# Mach_dieu_khien_dong_co_dc_luu_tru.net
KiCad netlist of a schematic drawn in Altium Designer
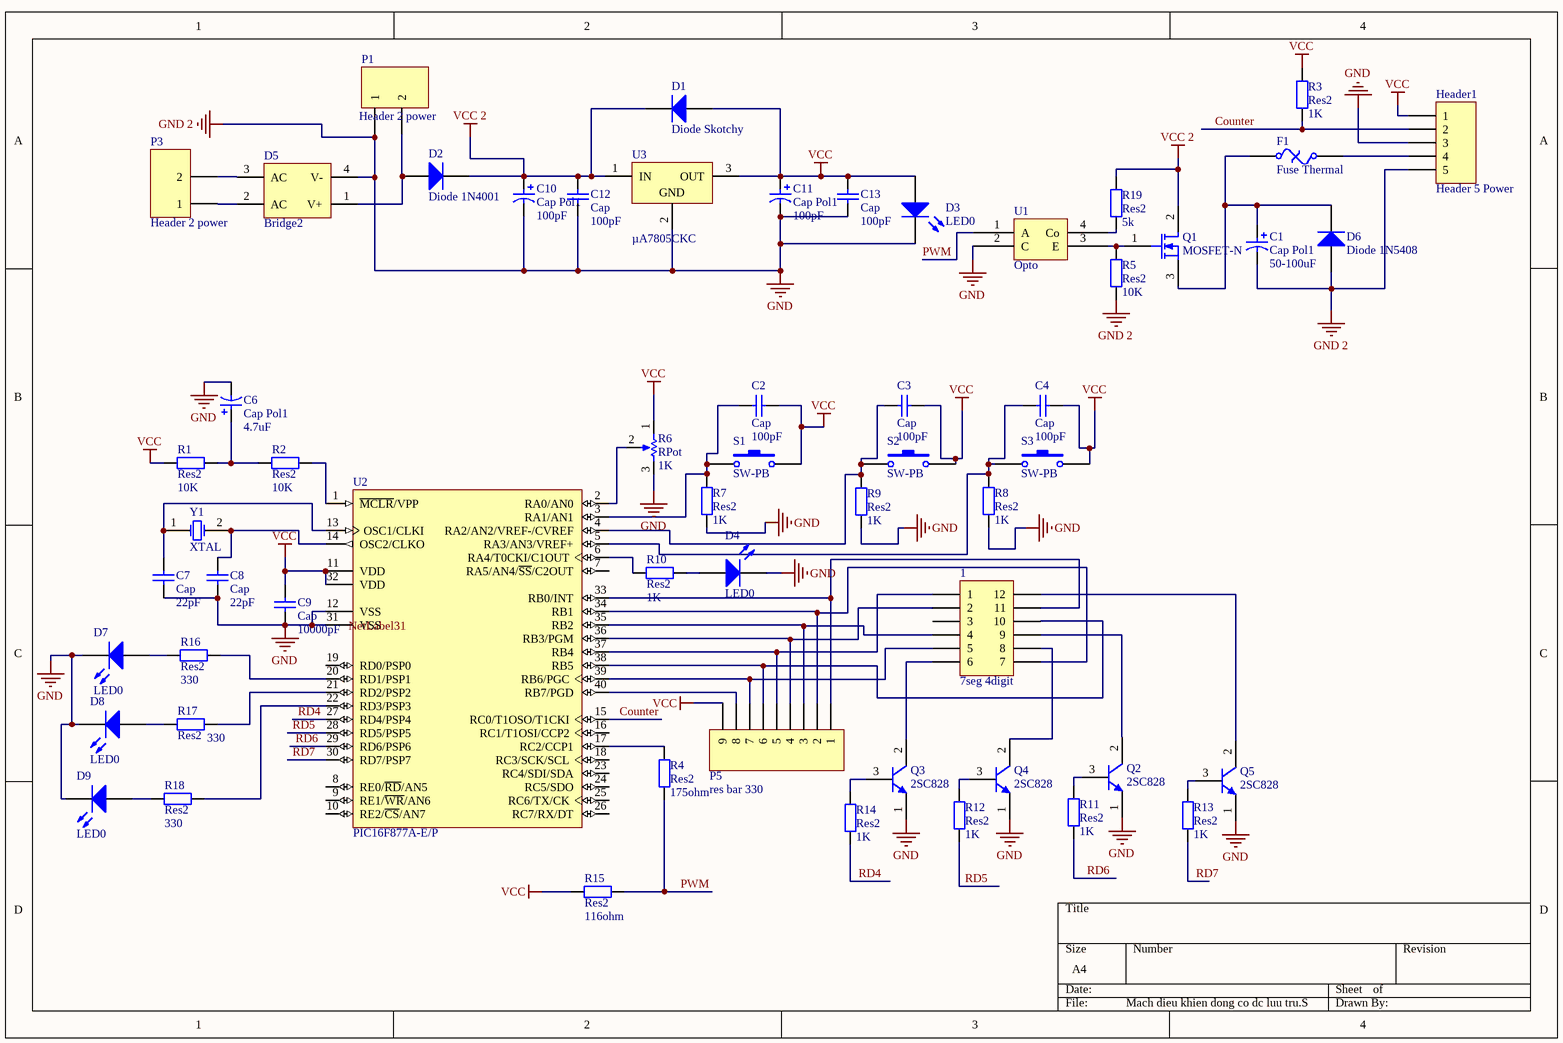
[diagram p0: Mach dieu khien dong co dc luu tru.SchDoc]

(export (version "E")
  (design (tool "Eeschema 10.0.6"))
  (components
    (comp (ref "1")
      (value "7seg 4digit")
      (footprint "LEDDIP-12/QUAD")
      (description "Header, 6-Pin, Dual row")
      (fields (field (name "PUBLISHER") "Altium Limited"))
      (libsource (lib "Manh") (part "7seg 4digit"))
    )
    (comp (ref "C1")
      (value "Cap Pol1")
      (footprint "CAPPR5-5x7")
      (description "Polarized Capacitor (Radial)")
      (fields (field (name "ALTIUM_VALUE") "50-100uF") (field (name "PUBLISHER") "Altium Limited"))
      (libsource (lib "Manh") (part "Cap Pol1"))
    )
    (comp (ref "C2")
      (value "Cap")
      (footprint "CAPNTO3.18-4.83x2.67")
      (description "Capacitor")
      (fields (field (name "ALTIUM_VALUE") "100pF") (field (name "PUBLISHER") "Altium Limited"))
      (libsource (lib "Manh") (part "Cap"))
    )
    (comp (ref "C3")
      (value "Cap")
      (footprint "CAPNTO3.18-4.83x2.67")
      (description "Capacitor")
      (fields (field (name "ALTIUM_VALUE") "100pF") (field (name "PUBLISHER") "Altium Limited"))
      (libsource (lib "Manh") (part "Cap"))
    )
    (comp (ref "C4")
      (value "Cap")
      (footprint "CAPNTO3.18-4.83x2.67")
      (description "Capacitor")
      (fields (field (name "ALTIUM_VALUE") "100pF") (field (name "PUBLISHER") "Altium Limited"))
      (libsource (lib "Manh") (part "Cap"))
    )
    (comp (ref "C6")
      (value "Cap Pol1")
      (footprint "CAPPR2-5x15")
      (description "Polarized Capacitor (Radial)")
      (fields (field (name "ALTIUM_VALUE") "4.7uF") (field (name "PUBLISHER") "Altium Limited"))
      (libsource (lib "Manh") (part "Cap Pol1"))
    )
    (comp (ref "C7")
      (value "Cap")
      (footprint "CAPNTO3.18-4.83x2.67")
      (description "Capacitor")
      (fields (field (name "ALTIUM_VALUE") "22pF") (field (name "PUBLISHER") "Altium Limited"))
      (libsource (lib "Manh") (part "Cap"))
    )
    (comp (ref "C8")
      (value "Cap")
      (footprint "CAPNTO3.18-4.83x2.67")
      (description "Capacitor")
      (fields (field (name "ALTIUM_VALUE") "22pF") (field (name "PUBLISHER") "Altium Limited"))
      (libsource (lib "Manh") (part "Cap"))
    )
    (comp (ref "C9")
      (value "Cap")
      (footprint "CAPNTO3.18-4.83x2.67")
      (description "Capacitor")
      (fields (field (name "ALTIUM_VALUE") "10000pF") (field (name "PUBLISHER") "Altium Limited"))
      (libsource (lib "Manh") (part "Cap"))
    )
    (comp (ref "C10")
      (value "Cap Pol1")
      (footprint "CAPPR7.5-18x40")
      (description "Polarized Capacitor (Radial)")
      (fields (field (name "ALTIUM_VALUE") "100pF") (field (name "PUBLISHER") "Altium Limited"))
      (libsource (lib "Manh") (part "Cap Pol1"))
    )
    (comp (ref "C11")
      (value "Cap Pol1")
      (footprint "CAPPR3.5-8x5")
      (description "Polarized Capacitor (Radial)")
      (fields (field (name "ALTIUM_VALUE") "100pF") (field (name "PUBLISHER") "Altium Limited"))
      (libsource (lib "Manh") (part "Cap Pol1"))
    )
    (comp (ref "C12")
      (value "Cap")
      (footprint "CAPNTO3.18-4.83x2.67")
      (description "Capacitor")
      (fields (field (name "ALTIUM_VALUE") "100pF") (field (name "PUBLISHER") "Altium Limited"))
      (libsource (lib "Manh") (part "Cap"))
    )
    (comp (ref "C13")
      (value "Cap")
      (footprint "CAPNTO3.18-4.83x2.67")
      (description "Capacitor")
      (fields (field (name "ALTIUM_VALUE") "100pF") (field (name "PUBLISHER") "Altium Limited"))
      (libsource (lib "Manh") (part "Cap"))
    )
    (comp (ref "D1")
      (value "Diode Skotchy")
      (footprint "DO-41")
      (description "1 Amp General Purpose Rectifier")
      (fields (field (name "PUBLISHER") "Altium Limited"))
      (libsource (lib "Miscellaneous Devices") (part "Diode 1N4001"))
    )
    (comp (ref "D2")
      (value "Diode 1N4001")
      (footprint "DO-41")
      (description "1 Amp General Purpose Rectifier")
      (fields (field (name "PUBLISHER") "Altium Limited"))
      (libsource (lib "Miscellaneous Devices") (part "Diode 1N4001"))
    )
    (comp (ref "D3")
      (value "LED0")
      (footprint "CAPPR2-5x15")
      (description "Typical INFRARED GaAs LED")
      (fields (field (name "PUBLISHER") "Altium Limited"))
      (libsource (lib "Manh") (part "LED0"))
    )
    (comp (ref "D4")
      (value "LED0")
      (footprint "CAPPR2-5x15")
      (description "Typical INFRARED GaAs LED")
      (fields (field (name "PUBLISHER") "Altium Limited"))
      (libsource (lib "Manh") (part "LED0"))
    )
    (comp (ref "D5")
      (value "Bridge2")
      (footprint "SIP-P4/A6.8")
      (description "Diode Bridge")
      (fields (field (name "PUBLISHER") "Altium Limited"))
      (libsource (lib "Manh") (part "Bridge2"))
    )
    (comp (ref "D6")
      (value "Diode 1N5408")
      (footprint "DO-201AD")
      (description "3 Amp Medium Power Silicon Rectifier Diode")
      (fields (field (name "PUBLISHER") "Altium Limited"))
      (libsource (lib "Miscellaneous Devices") (part "Diode 1N5408"))
    )
    (comp (ref "D7")
      (value "LED0")
      (footprint "CAPPR2-5x15")
      (description "Typical INFRARED GaAs LED")
      (fields (field (name "PUBLISHER") "Altium Limited"))
      (libsource (lib "Manh") (part "LED0"))
    )
    (comp (ref "D8")
      (value "LED0")
      (footprint "CAPPR2-5x15")
      (description "Typical INFRARED GaAs LED")
      (fields (field (name "PUBLISHER") "Altium Limited"))
      (libsource (lib "Manh") (part "LED0"))
    )
    (comp (ref "D9")
      (value "LED0")
      (footprint "CAPPR2-5x15")
      (description "Typical INFRARED GaAs LED")
      (fields (field (name "PUBLISHER") "Altium Limited"))
      (libsource (lib "Manh") (part "LED0"))
    )
    (comp (ref "F1")
      (value "Fuse Thermal")
      (footprint "PIN-W2/E2.8")
      (description "Thermal Fuse")
      (fields (field (name "PUBLISHER") "Altium Limited"))
      (libsource (lib "Manh") (part "Fuse Thermal"))
    )
    (comp (ref "Header1")
      (value "Header 5 Power")
      (footprint "Header 5 Power")
      (fields (field (name "PUBLISHER") "Altium Limited"))
      (libsource (lib "Manh") (part "Header 5 Power"))
    )
    (comp (ref "P1")
      (value "Header 2 power")
      (footprint "conector 2x1 power")
      (description "Header, 4-Pin, Right Angle")
      (fields (field (name "PUBLISHER") "Altium Limited"))
      (libsource (lib "Manh") (part "Header 2 power"))
    )
    (comp (ref "P3")
      (value "Header 2 power")
      (footprint "conector 2x1 power")
      (description "Header, 2-Pin, Right Angle")
      (fields (field (name "PUBLISHER") "Altium Limited"))
      (libsource (lib "") (part "Header 2 power_1"))
    )
    (comp (ref "P5")
      (value "res bar 330")
      (footprint "HDR1X9")
      (description "Header, 9-Pin")
      (fields (field (name "PUBLISHER") "Altium Limited"))
      (libsource (lib "Miscellaneous Connectors") (part "Header 9"))
    )
    (comp (ref "Q1")
      (value "MOSFET-N")
      (footprint "E3-manh")
      (description "N-Channel MOSFET")
      (fields (field (name "PUBLISHER") "Altium Limited"))
      (libsource (lib "Manh") (part "MOSFET-N"))
    )
    (comp (ref "Q2")
      (value "2SC828")
      (footprint "TO-92-manh")
      (description "NPN General Purpose Amplifier")
      (fields (field (name "PUBLISHER") "Altium Limited"))
      (libsource (lib "Manh") (part "2SC828"))
    )
    (comp (ref "Q3")
      (value "2SC828")
      (footprint "TO-92-manh")
      (description "NPN General Purpose Amplifier")
      (fields (field (name "PUBLISHER") "Altium Limited"))
      (libsource (lib "Manh") (part "2SC828"))
    )
    (comp (ref "Q4")
      (value "2SC828")
      (footprint "TO-92-manh")
      (description "NPN General Purpose Amplifier")
      (fields (field (name "PUBLISHER") "Altium Limited"))
      (libsource (lib "Manh") (part "2SC828"))
    )
    (comp (ref "Q5")
      (value "2SC828")
      (footprint "TO-92-manh")
      (description "NPN General Purpose Amplifier")
      (fields (field (name "PUBLISHER") "Altium Limited"))
      (libsource (lib "Manh") (part "2SC828"))
    )
    (comp (ref "R1")
      (value "Res2")
      (footprint "AXIAL-0.4")
      (description "Resistor")
      (fields (field (name "ALTIUM_VALUE") "10K") (field (name "PUBLISHER") "Altium Limited"))
      (libsource (lib "") (part "Res2_2"))
    )
    (comp (ref "R2")
      (value "Res2")
      (footprint "AXIAL-0.4")
      (description "Resistor")
      (fields (field (name "ALTIUM_VALUE") "10K") (field (name "PUBLISHER") "Altium Limited"))
      (libsource (lib "") (part "Res2_2"))
    )
    (comp (ref "R3")
      (value "Res2")
      (footprint "AXIAL-0.4")
      (description "Resistor")
      (fields (field (name "ALTIUM_VALUE") "1K") (field (name "PUBLISHER") "Altium Limited"))
      (libsource (lib "") (part "Res2_3"))
    )
    (comp (ref "R4")
      (value "Res2")
      (footprint "AXIAL-0.4")
      (description "Resistor")
      (fields (field (name "ALTIUM_VALUE") "175ohm") (field (name "PUBLISHER") "Altium Limited"))
      (libsource (lib "") (part "Res2_1"))
    )
    (comp (ref "R5")
      (value "Res2")
      (footprint "AXIAL-0.4")
      (description "Resistor")
      (fields (field (name "ALTIUM_VALUE") "10K") (field (name "PUBLISHER") "Altium Limited"))
      (libsource (lib "") (part "Res2_1"))
    )
    (comp (ref "R6")
      (value "RPot")
      (footprint "Header 3 Power")
      (description "Potentiometer")
      (fields (field (name "ALTIUM_VALUE") "1K") (field (name "PUBLISHER") "Altium Limited"))
      (libsource (lib "Manh") (part "RPot"))
    )
    (comp (ref "R7")
      (value "Res2")
      (footprint "AXIAL-0.4")
      (description "Resistor")
      (fields (field (name "ALTIUM_VALUE") "1K") (field (name "PUBLISHER") "Altium Limited"))
      (libsource (lib "") (part "Res2_1"))
    )
    (comp (ref "R8")
      (value "Res2")
      (footprint "AXIAL-0.4")
      (description "Resistor")
      (fields (field (name "ALTIUM_VALUE") "1K") (field (name "PUBLISHER") "Altium Limited"))
      (libsource (lib "") (part "Res2_1"))
    )
    (comp (ref "R9")
      (value "Res2")
      (footprint "AXIAL-0.4")
      (description "Resistor")
      (fields (field (name "ALTIUM_VALUE") "1K") (field (name "PUBLISHER") "Altium Limited"))
      (libsource (lib "") (part "Res2_1"))
    )
    (comp (ref "R10")
      (value "Res2")
      (footprint "AXIAL-0.4")
      (description "Resistor")
      (fields (field (name "ALTIUM_VALUE") "1K") (field (name "PUBLISHER") "Altium Limited"))
      (libsource (lib "") (part "Res2_2"))
    )
    (comp (ref "R11")
      (value "Res2")
      (footprint "AXIAL-0.4")
      (description "Resistor")
      (fields (field (name "ALTIUM_VALUE") "1K") (field (name "PUBLISHER") "Altium Limited"))
      (libsource (lib "") (part "Res2_1"))
    )
    (comp (ref "R12")
      (value "Res2")
      (footprint "AXIAL-0.4")
      (description "Resistor")
      (fields (field (name "ALTIUM_VALUE") "1K") (field (name "PUBLISHER") "Altium Limited"))
      (libsource (lib "") (part "Res2_1"))
    )
    (comp (ref "R13")
      (value "Res2")
      (footprint "AXIAL-0.4")
      (description "Resistor")
      (fields (field (name "ALTIUM_VALUE") "1K") (field (name "PUBLISHER") "Altium Limited"))
      (libsource (lib "") (part "Res2_1"))
    )
    (comp (ref "R14")
      (value "Res2")
      (footprint "AXIAL-0.4")
      (description "Resistor")
      (fields (field (name "ALTIUM_VALUE") "1K") (field (name "PUBLISHER") "Altium Limited"))
      (libsource (lib "") (part "Res2_1"))
    )
    (comp (ref "R15")
      (value "Res2")
      (footprint "AXIAL-0.4")
      (description "Resistor")
      (fields (field (name "ALTIUM_VALUE") "116ohm") (field (name "PUBLISHER") "Altium Limited"))
      (libsource (lib "Manh") (part "Res2"))
    )
    (comp (ref "R16")
      (value "Res2")
      (footprint "AXIAL-0.4")
      (description "Resistor")
      (fields (field (name "ALTIUM_VALUE") "330") (field (name "PUBLISHER") "Altium Limited"))
      (libsource (lib "") (part "Res2_2"))
    )
    (comp (ref "R17")
      (value "Res2")
      (footprint "AXIAL-0.4")
      (description "Resistor")
      (fields (field (name "ALTIUM_VALUE") "330") (field (name "PUBLISHER") "Altium Limited"))
      (libsource (lib "") (part "Res2_2"))
    )
    (comp (ref "R18")
      (value "Res2")
      (footprint "AXIAL-0.4")
      (description "Resistor")
      (fields (field (name "ALTIUM_VALUE") "330") (field (name "PUBLISHER") "Altium Limited"))
      (libsource (lib "") (part "Res2_2"))
    )
    (comp (ref "R19")
      (value "Res2")
      (footprint "AXIAL-0.4")
      (description "Resistor")
      (fields (field (name "ALTIUM_VALUE") "5k") (field (name "PUBLISHER") "Altium Limited"))
      (libsource (lib "") (part "Res2_1"))
    )
    (comp (ref "S1")
      (value "SW-PB")
      (footprint "Button DIP4")
      (description "Switch")
      (fields (field (name "PUBLISHER") "Altium Limited"))
      (libsource (lib "Manh") (part "SW-PB"))
    )
    (comp (ref "S2")
      (value "SW-PB")
      (footprint "Button DIP4")
      (description "Switch")
      (fields (field (name "PUBLISHER") "Altium Limited"))
      (libsource (lib "Manh") (part "SW-PB"))
    )
    (comp (ref "S3")
      (value "SW-PB")
      (footprint "Button DIP4")
      (description "Switch")
      (fields (field (name "PUBLISHER") "Altium Limited"))
      (libsource (lib "Manh") (part "SW-PB"))
    )
    (comp (ref "U1") (value "Opto") (footprint "DIP-4") (libsource (lib "Manh") (part "Opto 1")))
    (comp (ref "U2")
      (value "PIC16F877A-E/P")
      (footprint "Microchip Footprints:PDIP600-40")
      (fields (field (name "PUBLISHER") "Altium Limited"))
      (libsource (lib "Manh") (part "PIC16F877A-E/P"))
    )
    (comp (ref "U3")
      (value "µA7805CKC")
      (footprint "SFM-T3/A4.7V")
      (description "Positive-Voltage Regulator")
      (fields (field (name "MANUFACTURER") "Texas Instruments") (field (name "PUBLISHER") "Altium Limited"))
      (libsource (lib "TI Power Mgt Voltage Regulator") (part "µA7805CKC"))
    )
    (comp (ref "Y1")
      (value "XTAL")
      (footprint "CAPR5-4X5")
      (description "Crystal Oscillator")
      (fields (field (name "PUBLISHER") "Altium Limited"))
      (libsource (lib "Manh") (part "XTAL"))
    )
  )
  (nets
    (net (code "1") (name "/Counter") (class "Default")
      (node (ref "Header1") (pin "2") (pinfunction "2_2") (pintype "passive"))
      (node (ref "R3") (pin "2") (pinfunction "2_2") (pintype "passive"))
      (node (ref "U2") (pin "15") (pinfunction "RC0/T1OSO/T1CKI_15") (pintype "bidirectional"))
    )
    (net (code "3") (name "/PWM") (class "Default")
      (node (ref "R15") (pin "1") (pinfunction "1_1") (pintype "passive"))
      (node (ref "R4") (pin "1") (pinfunction "1_1") (pintype "passive"))
      (node (ref "U1") (pin "1") (pinfunction "A_1") (pintype "passive"))
    )
    (net (code "4") (name "/RD4") (class "Default")
      (node (ref "R14") (pin "1") (pinfunction "1_1") (pintype "passive"))
      (node (ref "U2") (pin "27") (pinfunction "RD4/PSP4_27") (pintype "bidirectional"))
    )
    (net (code "5") (name "/RD5") (class "Default")
      (node (ref "R12") (pin "1") (pinfunction "1_1") (pintype "passive"))
      (node (ref "U2") (pin "28") (pinfunction "RD5/PSP5_28") (pintype "bidirectional"))
    )
    (net (code "6") (name "/RD6") (class "Default")
      (node (ref "R11") (pin "1") (pinfunction "1_1") (pintype "passive"))
      (node (ref "U2") (pin "29") (pinfunction "RD6/PSP6_29") (pintype "bidirectional"))
    )
    (net (code "7") (name "/RD7") (class "Default")
      (node (ref "R13") (pin "1") (pinfunction "1_1") (pintype "passive"))
      (node (ref "U2") (pin "30") (pinfunction "RD7/PSP7_30") (pintype "bidirectional"))
    )
    (net (code "8") (name "GND") (class "Default")
      (node (ref "C1") (pin "2") (pinfunction "2_2") (pintype "passive"))
      (node (ref "C10") (pin "2") (pinfunction "2_2") (pintype "passive"))
      (node (ref "C11") (pin "2") (pinfunction "2_2") (pintype "passive"))
      (node (ref "C12") (pin "1") (pinfunction "1_1") (pintype "passive"))
      (node (ref "C13") (pin "1") (pinfunction "1_1") (pintype "passive"))
      (node (ref "C6") (pin "2") (pinfunction "2_2") (pintype "passive"))
      (node (ref "C7") (pin "1") (pinfunction "1_1") (pintype "passive"))
      (node (ref "C8") (pin "1") (pinfunction "1_1") (pintype "passive"))
      (node (ref "C9") (pin "1") (pinfunction "1_1") (pintype "passive"))
      (node (ref "D3") (pin "2") (pinfunction "K_2") (pintype "passive"))
      (node (ref "D4") (pin "2") (pinfunction "K_2") (pintype "passive"))
      (node (ref "D5") (pin "4") (pinfunction "V-_4") (pintype "passive"))
      (node (ref "D6") (pin "1") (pinfunction "A_1") (pintype "passive"))
      (node (ref "D7") (pin "2") (pinfunction "K_2") (pintype "passive"))
      (node (ref "D8") (pin "2") (pinfunction "K_2") (pintype "passive"))
      (node (ref "D9") (pin "2") (pinfunction "K_2") (pintype "passive"))
      (node (ref "Header1") (pin "3") (pinfunction "3_3") (pintype "passive"))
      (node (ref "Header1") (pin "5") (pinfunction "5_5") (pintype "passive"))
      (node (ref "P1") (pin "1") (pinfunction "1_1") (pintype "passive"))
      (node (ref "Q2") (pin "1") (pinfunction "E_1") (pintype "passive"))
      (node (ref "Q3") (pin "1") (pinfunction "E_1") (pintype "passive"))
      (node (ref "Q4") (pin "1") (pinfunction "E_1") (pintype "passive"))
      (node (ref "Q5") (pin "1") (pinfunction "E_1") (pintype "passive"))
      (node (ref "R5") (pin "1") (pinfunction "1_1") (pintype "passive"))
      (node (ref "R6") (pin "3") (pinfunction "BOT_3") (pintype "passive"))
      (node (ref "R7") (pin "1") (pinfunction "1_1") (pintype "passive"))
      (node (ref "R8") (pin "1") (pinfunction "1_1") (pintype "passive"))
      (node (ref "R9") (pin "1") (pinfunction "1_1") (pintype "passive"))
      (node (ref "U1") (pin "2") (pinfunction "C_2") (pintype "passive"))
      (node (ref "U2") (pin "12") (pinfunction "VSS_12") (pintype "power_in"))
      (node (ref "U2") (pin "31") (pinfunction "VSS_31") (pintype "power_in"))
      (node (ref "U3") (pin "2") (pinfunction "GND_2") (pintype "power_in"))
    )
    (net (code "9") (name "Net-(C6-Pad1)") (class "Default")
      (node (ref "C6") (pin "1") (pinfunction "1_1") (pintype "passive"))
      (node (ref "R1") (pin "2") (pinfunction "2_2") (pintype "passive"))
      (node (ref "R2") (pin "1") (pinfunction "1_1") (pintype "passive"))
    )
    (net (code "10") (name "Net-(D2-A)") (class "Default")
      (node (ref "D2") (pin "1") (pinfunction "A_1") (pintype "passive"))
      (node (ref "D5") (pin "1") (pinfunction "V+_1") (pintype "passive"))
      (node (ref "P1") (pin "2") (pinfunction "2_2") (pintype "passive"))
    )
    (net (code "11") (name "Net-(D4-A)") (class "Default")
      (node (ref "D4") (pin "1") (pinfunction "A_1") (pintype "passive"))
      (node (ref "R10") (pin "2") (pinfunction "2_2") (pintype "passive"))
    )
    (net (code "12") (name "Net-(D5-AC-Pad2)") (class "Default")
      (node (ref "D5") (pin "2") (pinfunction "AC_2") (pintype "passive"))
      (node (ref "P3") (pin "1") (pinfunction "1_1") (pintype "passive"))
    )
    (net (code "13") (name "Net-(D5-AC-Pad3)") (class "Default")
      (node (ref "D5") (pin "3") (pinfunction "AC_3") (pintype "passive"))
      (node (ref "P3") (pin "2") (pinfunction "2_2") (pintype "passive"))
    )
    (net (code "14") (name "Net-(D6-K)") (class "Default")
      (node (ref "C1") (pin "1") (pinfunction "1_1") (pintype "passive"))
      (node (ref "D6") (pin "2") (pinfunction "K_2") (pintype "passive"))
      (node (ref "F1") (pin "1") (pinfunction "1_1") (pintype "passive"))
      (node (ref "Q1") (pin "3") (pinfunction "S_3") (pintype "passive"))
    )
    (net (code "15") (name "Net-(D7-A)") (class "Default")
      (node (ref "D7") (pin "1") (pinfunction "A_1") (pintype "passive"))
      (node (ref "R16") (pin "1") (pinfunction "1_1") (pintype "passive"))
    )
    (net (code "16") (name "Net-(D8-A)") (class "Default")
      (node (ref "D8") (pin "1") (pinfunction "A_1") (pintype "passive"))
      (node (ref "R17") (pin "1") (pinfunction "1_1") (pintype "passive"))
    )
    (net (code "17") (name "Net-(D9-A)") (class "Default")
      (node (ref "D9") (pin "1") (pinfunction "A_1") (pintype "passive"))
      (node (ref "R18") (pin "1") (pinfunction "1_1") (pintype "passive"))
    )
    (net (code "18") (name "Net-(F1-Pad2)") (class "Default")
      (node (ref "F1") (pin "2") (pinfunction "2_2") (pintype "passive"))
      (node (ref "Header1") (pin "4") (pinfunction "4_4") (pintype "passive"))
    )
    (net (code "19") (name "Net-(Q1-G)") (class "Default")
      (node (ref "Q1") (pin "1") (pinfunction "G_1") (pintype "passive"))
      (node (ref "R5") (pin "2") (pinfunction "2_2") (pintype "passive"))
      (node (ref "U1") (pin "3") (pinfunction "E_3") (pintype "passive"))
    )
    (net (code "20") (name "Net-(Q2-B)") (class "Default")
      (node (ref "Q2") (pin "3") (pinfunction "B_3") (pintype "passive"))
      (node (ref "R11") (pin "2") (pinfunction "2_2") (pintype "passive"))
    )
    (net (code "21") (name "Net-(Q2-C)") (class "Default")
      (node (ref "1") (pin "9") (pinfunction "9_9") (pintype "passive"))
      (node (ref "Q2") (pin "2") (pinfunction "C_2") (pintype "passive"))
    )
    (net (code "22") (name "Net-(Q3-B)") (class "Default")
      (node (ref "Q3") (pin "3") (pinfunction "B_3") (pintype "passive"))
      (node (ref "R14") (pin "2") (pinfunction "2_2") (pintype "passive"))
    )
    (net (code "23") (name "Net-(Q3-C)") (class "Default")
      (node (ref "1") (pin "6") (pinfunction "6_6") (pintype "passive"))
      (node (ref "Q3") (pin "2") (pinfunction "C_2") (pintype "passive"))
    )
    (net (code "24") (name "Net-(Q4-B)") (class "Default")
      (node (ref "Q4") (pin "3") (pinfunction "B_3") (pintype "passive"))
      (node (ref "R12") (pin "2") (pinfunction "2_2") (pintype "passive"))
    )
    (net (code "25") (name "Net-(Q4-C)") (class "Default")
      (node (ref "1") (pin "8") (pinfunction "8_8") (pintype "passive"))
      (node (ref "Q4") (pin "2") (pinfunction "C_2") (pintype "passive"))
    )
    (net (code "26") (name "Net-(Q5-B)") (class "Default")
      (node (ref "Q5") (pin "3") (pinfunction "B_3") (pintype "passive"))
      (node (ref "R13") (pin "2") (pinfunction "2_2") (pintype "passive"))
    )
    (net (code "27") (name "Net-(Q5-C)") (class "Default")
      (node (ref "1") (pin "12") (pinfunction "12_12") (pintype "passive"))
      (node (ref "Q5") (pin "2") (pinfunction "C_2") (pintype "passive"))
    )
    (net (code "28") (name "Net-(R6-TAP)") (class "Default")
      (node (ref "R6") (pin "2") (pinfunction "TAP_2") (pintype "passive"))
      (node (ref "U2") (pin "2") (pinfunction "RA0/AN0_2") (pintype "bidirectional"))
    )
    (net (code "29") (name "Net-(U1-Co)") (class "Default")
      (node (ref "R19") (pin "1") (pinfunction "1_1") (pintype "passive"))
      (node (ref "U1") (pin "4") (pinfunction "Co_4") (pintype "passive"))
    )
    (net (code "30") (name "Net-(U2-OSC1{slash}CLKI)") (class "Default")
      (node (ref "C7") (pin "2") (pinfunction "2_2") (pintype "passive"))
      (node (ref "U2") (pin "13") (pinfunction "OSC1/CLKI_13") (pintype "input"))
      (node (ref "Y1") (pin "1") (pinfunction "OSC1_1") (pintype "passive"))
    )
    (net (code "31") (name "Net-(U2-OSC2{slash}CLKO)") (class "Default")
      (node (ref "C8") (pin "2") (pinfunction "2_2") (pintype "passive"))
      (node (ref "U2") (pin "14") (pinfunction "OSC2/CLKO_14") (pintype "output"))
      (node (ref "Y1") (pin "2") (pinfunction "OSC2_2") (pintype "passive"))
    )
    (net (code "32") (name "Net-(U2-RA1{slash}AN1)") (class "Default")
      (node (ref "C2") (pin "1") (pinfunction "1_1") (pintype "passive"))
      (node (ref "R7") (pin "2") (pinfunction "2_2") (pintype "passive"))
      (node (ref "S1") (pin "1") (pinfunction "1_1") (pintype "passive"))
      (node (ref "U2") (pin "3") (pinfunction "RA1/AN1_3") (pintype "bidirectional"))
    )
    (net (code "33") (name "Net-(U2-RA2{slash}AN2{slash}VREF-{slash}CVREF)") (class "Default")
      (node (ref "C3") (pin "1") (pinfunction "1_1") (pintype "passive"))
      (node (ref "R9") (pin "2") (pinfunction "2_2") (pintype "passive"))
      (node (ref "S2") (pin "1") (pinfunction "1_1") (pintype "passive"))
      (node (ref "U2") (pin "4") (pinfunction "RA2/AN2/VREF-/CVREF_4") (pintype "bidirectional"))
    )
    (net (code "34") (name "Net-(U2-RA3{slash}AN3{slash}VREF+)") (class "Default")
      (node (ref "C4") (pin "1") (pinfunction "1_1") (pintype "passive"))
      (node (ref "R8") (pin "2") (pinfunction "2_2") (pintype "passive"))
      (node (ref "S3") (pin "1") (pinfunction "1_1") (pintype "passive"))
      (node (ref "U2") (pin "5") (pinfunction "RA3/AN3/VREF+_5") (pintype "bidirectional"))
    )
    (net (code "35") (name "Net-(U2-RA4{slash}T0CKI{slash}C1OUT)") (class "Default")
      (node (ref "R10") (pin "1") (pinfunction "1_1") (pintype "passive"))
      (node (ref "U2") (pin "6") (pinfunction "RA4/T0CKI/C1OUT_6") (pintype "bidirectional"))
    )
    (net (code "36") (name "Net-(U2-RB0{slash}INT)") (class "Default")
      (node (ref "1") (pin "11") (pinfunction "11_11") (pintype "passive"))
      (node (ref "P5") (pin "1") (pinfunction "1_1") (pintype "passive"))
      (node (ref "U2") (pin "33") (pinfunction "RB0/INT_33") (pintype "bidirectional"))
    )
    (net (code "37") (name "Net-(U2-RB1)") (class "Default")
      (node (ref "1") (pin "7") (pinfunction "7_7") (pintype "passive"))
      (node (ref "P5") (pin "2") (pinfunction "2_2") (pintype "passive"))
      (node (ref "U2") (pin "34") (pinfunction "RB1_34") (pintype "bidirectional"))
    )
    (net (code "38") (name "Net-(U2-RB2)") (class "Default")
      (node (ref "1") (pin "4") (pinfunction "4_4") (pintype "passive"))
      (node (ref "P5") (pin "3") (pinfunction "3_3") (pintype "passive"))
      (node (ref "U2") (pin "35") (pinfunction "RB2_35") (pintype "bidirectional"))
    )
    (net (code "39") (name "Net-(U2-RB3{slash}PGM)") (class "Default")
      (node (ref "1") (pin "2") (pinfunction "2_2") (pintype "passive"))
      (node (ref "P5") (pin "4") (pinfunction "4_4") (pintype "passive"))
      (node (ref "U2") (pin "36") (pinfunction "RB3/PGM_36") (pintype "bidirectional"))
    )
    (net (code "40") (name "Net-(U2-RB4)") (class "Default")
      (node (ref "1") (pin "1") (pinfunction "1_1") (pintype "passive"))
      (node (ref "P5") (pin "5") (pinfunction "5_5") (pintype "passive"))
      (node (ref "U2") (pin "37") (pinfunction "RB4_37") (pintype "bidirectional"))
    )
    (net (code "41") (name "Net-(U2-RB5)") (class "Default")
      (node (ref "1") (pin "10") (pinfunction "10_10") (pintype "passive"))
      (node (ref "P5") (pin "6") (pinfunction "6_6") (pintype "passive"))
      (node (ref "U2") (pin "38") (pinfunction "RB5_38") (pintype "bidirectional"))
    )
    (net (code "42") (name "Net-(U2-RB6{slash}PGC)") (class "Default")
      (node (ref "1") (pin "5") (pinfunction "5_5") (pintype "passive"))
      (node (ref "P5") (pin "7") (pinfunction "7_7") (pintype "passive"))
      (node (ref "U2") (pin "39") (pinfunction "RB6/PGC_39") (pintype "bidirectional"))
    )
    (net (code "43") (name "Net-(U2-RB7{slash}PGD)") (class "Default")
      (node (ref "P5") (pin "8") (pinfunction "8_8") (pintype "passive"))
      (node (ref "U2") (pin "40") (pinfunction "RB7/PGD_40") (pintype "bidirectional"))
    )
    (net (code "44") (name "Net-(U2-RC2{slash}CCP1)") (class "Default")
      (node (ref "R4") (pin "2") (pinfunction "2_2") (pintype "passive"))
      (node (ref "U2") (pin "17") (pinfunction "RC2/CCP1_17") (pintype "bidirectional"))
    )
    (net (code "45") (name "Net-(U2-RD1{slash}PSP1)") (class "Default")
      (node (ref "R16") (pin "2") (pinfunction "2_2") (pintype "passive"))
      (node (ref "U2") (pin "20") (pinfunction "RD1/PSP1_20") (pintype "bidirectional"))
    )
    (net (code "46") (name "Net-(U2-RD2{slash}PSP2)") (class "Default")
      (node (ref "R17") (pin "2") (pinfunction "2_2") (pintype "passive"))
      (node (ref "U2") (pin "21") (pinfunction "RD2/PSP2_21") (pintype "bidirectional"))
    )
    (net (code "47") (name "Net-(U2-RD3{slash}PSP3)") (class "Default")
      (node (ref "R18") (pin "2") (pinfunction "2_2") (pintype "passive"))
      (node (ref "U2") (pin "22") (pinfunction "RD3/PSP3_22") (pintype "bidirectional"))
    )
    (net (code "48") (name "Net-(U2-~{MCLR}{slash}VPP)") (class "Default")
      (node (ref "R2") (pin "2") (pinfunction "2_2") (pintype "passive"))
      (node (ref "U2") (pin "1") (pinfunction "~{MCLR}/VPP_1") (pintype "input"))
    )
    (net (code "49") (name "VCC") (class "Default")
      (node (ref "C11") (pin "1") (pinfunction "1_1") (pintype "passive"))
      (node (ref "C13") (pin "2") (pinfunction "2_2") (pintype "passive"))
      (node (ref "C2") (pin "2") (pinfunction "2_2") (pintype "passive"))
      (node (ref "C3") (pin "2") (pinfunction "2_2") (pintype "passive"))
      (node (ref "C4") (pin "2") (pinfunction "2_2") (pintype "passive"))
      (node (ref "C9") (pin "2") (pinfunction "2_2") (pintype "passive"))
      (node (ref "D1") (pin "1") (pinfunction "A_1") (pintype "passive"))
      (node (ref "D3") (pin "1") (pinfunction "A_1") (pintype "passive"))
      (node (ref "Header1") (pin "1") (pinfunction "1_1") (pintype "passive"))
      (node (ref "P5") (pin "9") (pinfunction "9_9") (pintype "passive"))
      (node (ref "R1") (pin "1") (pinfunction "1_1") (pintype "passive"))
      (node (ref "R15") (pin "2") (pinfunction "2_2") (pintype "passive"))
      (node (ref "R3") (pin "1") (pinfunction "1_1") (pintype "passive"))
      (node (ref "R6") (pin "1") (pinfunction "TOP_1") (pintype "passive"))
      (node (ref "S1") (pin "2") (pinfunction "2_2") (pintype "passive"))
      (node (ref "S2") (pin "2") (pinfunction "2_2") (pintype "passive"))
      (node (ref "S3") (pin "2") (pinfunction "2_2") (pintype "passive"))
      (node (ref "U2") (pin "11") (pinfunction "VDD_11") (pintype "power_in"))
      (node (ref "U2") (pin "32") (pinfunction "VDD_32") (pintype "power_in"))
      (node (ref "U3") (pin "3") (pinfunction "OUT_3") (pintype "power_in"))
    )
    (net (code "50") (name "VCC 2") (class "Default")
      (node (ref "C10") (pin "1") (pinfunction "1_1") (pintype "passive"))
      (node (ref "C12") (pin "2") (pinfunction "2_2") (pintype "passive"))
      (node (ref "D1") (pin "2") (pinfunction "K_2") (pintype "passive"))
      (node (ref "D2") (pin "2") (pinfunction "K_2") (pintype "passive"))
      (node (ref "Q1") (pin "2") (pinfunction "D_2") (pintype "passive"))
      (node (ref "R19") (pin "2") (pinfunction "2_2") (pintype "passive"))
      (node (ref "U3") (pin "1") (pinfunction "IN_1") (pintype "power_in"))
    )
    (net (code "51") (name "unconnected-(1-Pad3)") (class "Default")
      (node (ref "1") (pin "3") (pinfunction "3_3") (pintype "passive"))
    )
    (net (code "52") (name "unconnected-(U2-RA5{slash}AN4{slash}~{SS}{slash}C2OUT-Pad7)") (class "Default")
      (node (ref "U2") (pin "7") (pinfunction "RA5/AN4/~{SS}/C2OUT_7") (pintype "bidirectional"))
    )
    (net (code "53") (name "unconnected-(U2-RC1{slash}T1OSI{slash}CCP2-Pad16)") (class "Default")
      (node (ref "U2") (pin "16") (pinfunction "RC1/T1OSI/CCP2_16") (pintype "bidirectional"))
    )
    (net (code "54") (name "unconnected-(U2-RC3{slash}SCK{slash}SCL-Pad18)") (class "Default")
      (node (ref "U2") (pin "18") (pinfunction "RC3/SCK/SCL_18") (pintype "bidirectional"))
    )
    (net (code "55") (name "unconnected-(U2-RC4{slash}SDI{slash}SDA-Pad23)") (class "Default")
      (node (ref "U2") (pin "23") (pinfunction "RC4/SDI/SDA_23") (pintype "bidirectional"))
    )
    (net (code "56") (name "unconnected-(U2-RC5{slash}SDO-Pad24)") (class "Default")
      (node (ref "U2") (pin "24") (pinfunction "RC5/SDO_24") (pintype "bidirectional"))
    )
    (net (code "57") (name "unconnected-(U2-RC6{slash}TX{slash}CK-Pad25)") (class "Default")
      (node (ref "U2") (pin "25") (pinfunction "RC6/TX/CK_25") (pintype "bidirectional"))
    )
    (net (code "58") (name "unconnected-(U2-RC7{slash}RX{slash}DT-Pad26)") (class "Default")
      (node (ref "U2") (pin "26") (pinfunction "RC7/RX/DT_26") (pintype "bidirectional"))
    )
    (net (code "59") (name "unconnected-(U2-RD0{slash}PSP0-Pad19)") (class "Default")
      (node (ref "U2") (pin "19") (pinfunction "RD0/PSP0_19") (pintype "bidirectional"))
    )
    (net (code "60") (name "unconnected-(U2-RE0{slash}~{RD}{slash}AN5-Pad8)") (class "Default")
      (node (ref "U2") (pin "8") (pinfunction "RE0/~{RD}/AN5_8") (pintype "bidirectional"))
    )
    (net (code "61") (name "unconnected-(U2-RE1{slash}~{WR}{slash}AN6-Pad9)") (class "Default")
      (node (ref "U2") (pin "9") (pinfunction "RE1/~{WR}/AN6_9") (pintype "bidirectional"))
    )
    (net (code "62") (name "unconnected-(U2-RE2{slash}~{CS}{slash}AN7-Pad10)") (class "Default")
      (node (ref "U2") (pin "10") (pinfunction "RE2/~{CS}/AN7_10") (pintype "bidirectional"))
    )
  )
)
